# ESP01M_Carrier.net
KiCad netlist of a schematic drawn in EAGLE
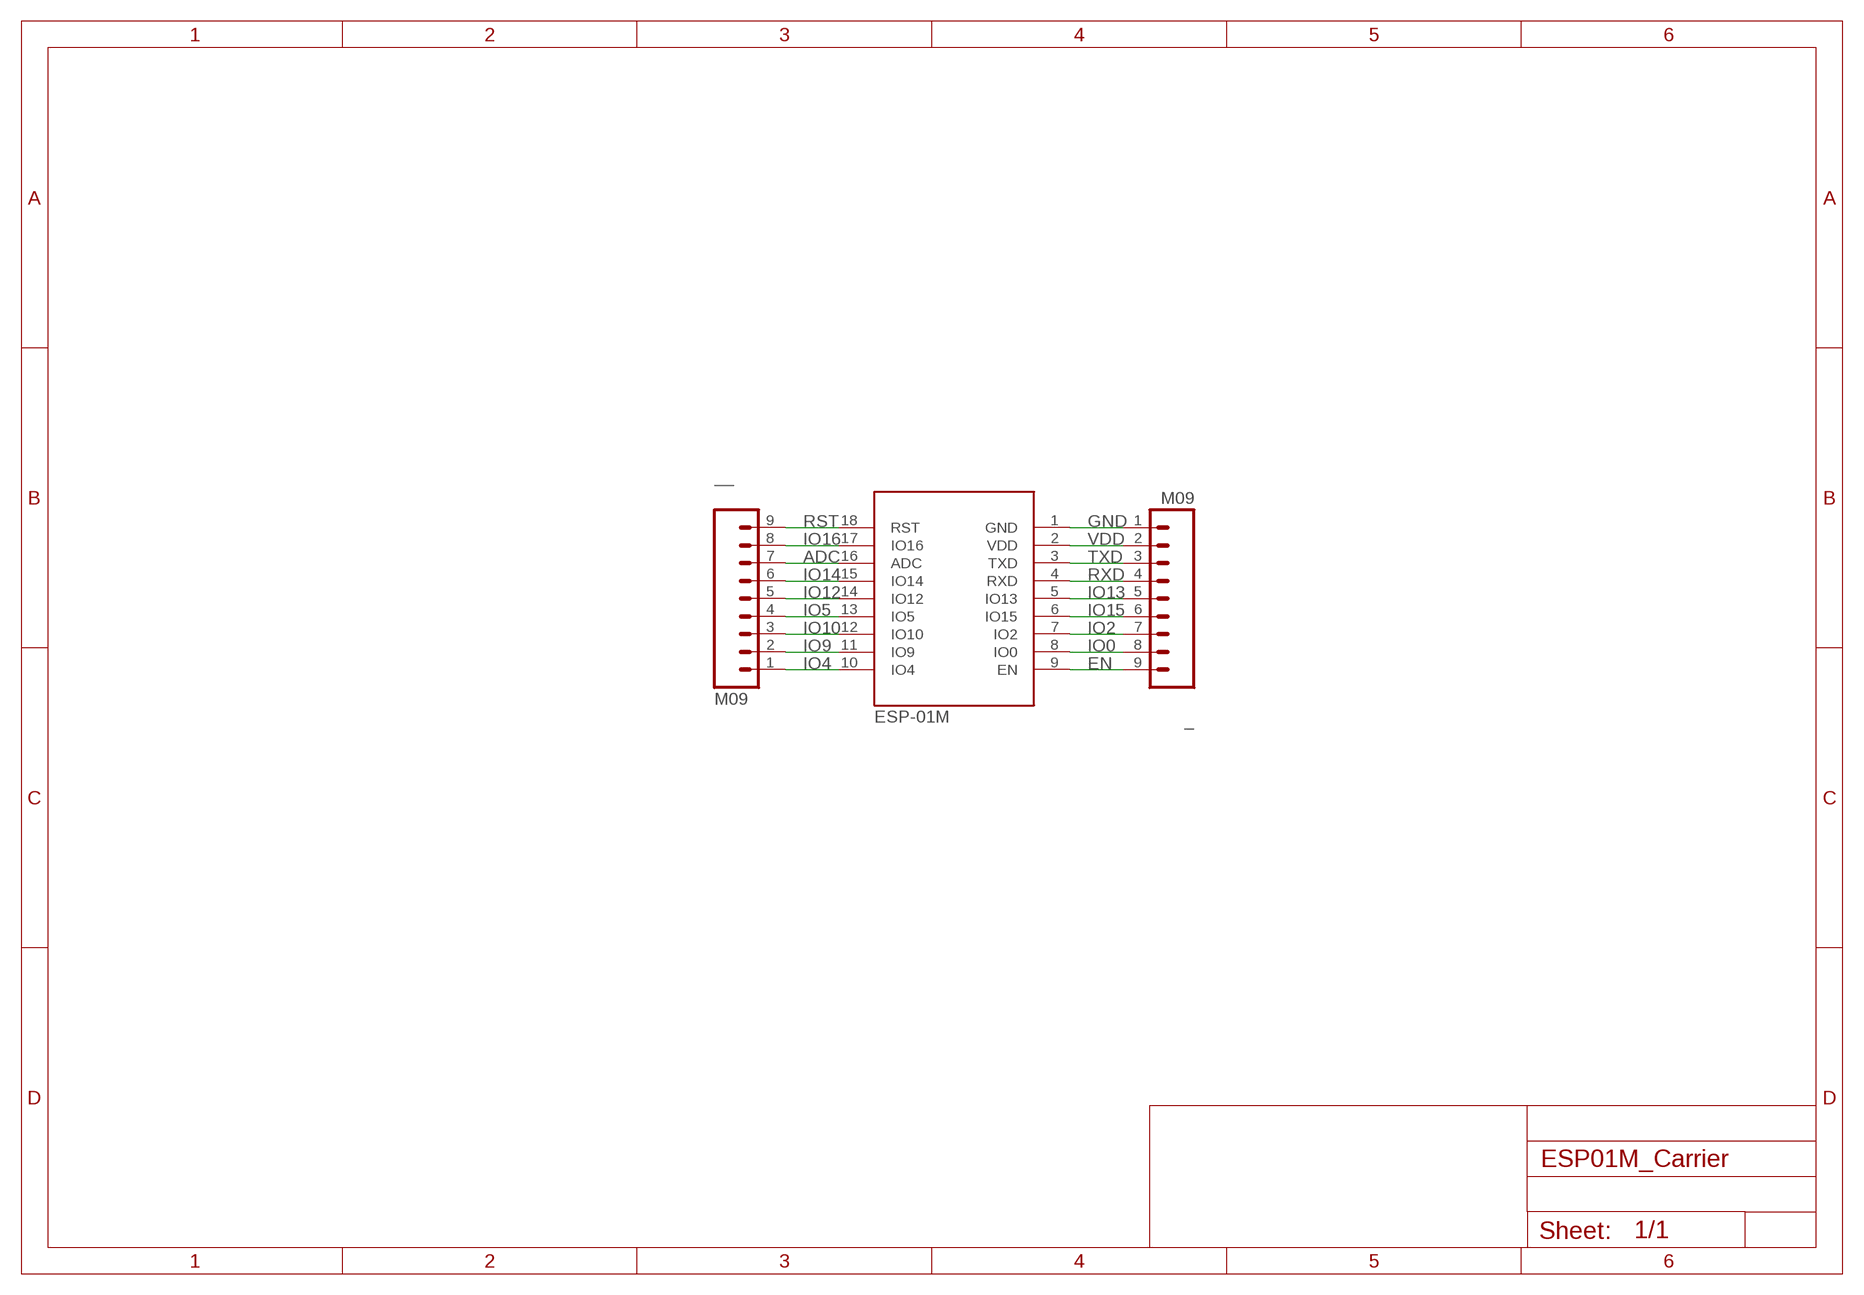
[diagram p0: schematic, sheet 1]

(export (version "E")
  (design (tool "Eeschema 10.0.6"))
  (components
    (comp (ref "ESP-01M")
      (value "ESP-01M")
      (footprint "eagle-import:ESP-01M")
      (libsource (lib "eagle-import") (part "ESP-01M"))
    )
    (comp (ref "_")
      (value "M09")
      (footprint "eagle-import:1X09")
      (libsource (lib "eagle-import") (part "M09"))
    )
    (comp (ref "__")
      (value "M09")
      (footprint "eagle-import:1X09")
      (libsource (lib "eagle-import") (part "M09"))
    )
  )
  (nets
    (net (code "1") (name "/ADC") (class "Default")
      (node (ref "ESP-01M") (pin "16") (pinfunction "ADC_16") (pintype "bidirectional"))
      (node (ref "__") (pin "7") (pinfunction "7_7") (pintype "passive"))
    )
    (net (code "2") (name "/EN") (class "Default")
      (node (ref "ESP-01M") (pin "9") (pinfunction "EN_9") (pintype "input"))
      (node (ref "_") (pin "9") (pinfunction "9_9") (pintype "passive"))
    )
    (net (code "3") (name "/GND") (class "Default")
      (node (ref "ESP-01M") (pin "1") (pinfunction "GND_1") (pintype "power_in"))
      (node (ref "_") (pin "1") (pinfunction "1_1") (pintype "passive"))
    )
    (net (code "4") (name "/IO0") (class "Default")
      (node (ref "ESP-01M") (pin "8") (pinfunction "IO0_8") (pintype "bidirectional"))
      (node (ref "_") (pin "8") (pinfunction "8_8") (pintype "passive"))
    )
    (net (code "5") (name "/IO2") (class "Default")
      (node (ref "ESP-01M") (pin "7") (pinfunction "IO2_7") (pintype "bidirectional"))
      (node (ref "_") (pin "7") (pinfunction "7_7") (pintype "passive"))
    )
    (net (code "6") (name "/IO4") (class "Default")
      (node (ref "ESP-01M") (pin "10") (pinfunction "IO4_10") (pintype "bidirectional"))
      (node (ref "__") (pin "1") (pinfunction "1_1") (pintype "passive"))
    )
    (net (code "7") (name "/IO5") (class "Default")
      (node (ref "ESP-01M") (pin "13") (pinfunction "IO5_13") (pintype "bidirectional"))
      (node (ref "__") (pin "4") (pinfunction "4_4") (pintype "passive"))
    )
    (net (code "8") (name "/IO9") (class "Default")
      (node (ref "ESP-01M") (pin "11") (pinfunction "IO9_11") (pintype "bidirectional"))
      (node (ref "__") (pin "2") (pinfunction "2_2") (pintype "passive"))
    )
    (net (code "9") (name "/IO10") (class "Default")
      (node (ref "ESP-01M") (pin "12") (pinfunction "IO10_12") (pintype "bidirectional"))
      (node (ref "__") (pin "3") (pinfunction "3_3") (pintype "passive"))
    )
    (net (code "10") (name "/IO12") (class "Default")
      (node (ref "ESP-01M") (pin "14") (pinfunction "IO12_14") (pintype "bidirectional"))
      (node (ref "__") (pin "5") (pinfunction "5_5") (pintype "passive"))
    )
    (net (code "11") (name "/IO13") (class "Default")
      (node (ref "ESP-01M") (pin "5") (pinfunction "IO13_5") (pintype "bidirectional"))
      (node (ref "_") (pin "5") (pinfunction "5_5") (pintype "passive"))
    )
    (net (code "12") (name "/IO14") (class "Default")
      (node (ref "ESP-01M") (pin "15") (pinfunction "IO14_15") (pintype "bidirectional"))
      (node (ref "__") (pin "6") (pinfunction "6_6") (pintype "passive"))
    )
    (net (code "13") (name "/IO15") (class "Default")
      (node (ref "ESP-01M") (pin "6") (pinfunction "IO15_6") (pintype "bidirectional"))
      (node (ref "_") (pin "6") (pinfunction "6_6") (pintype "passive"))
    )
    (net (code "14") (name "/IO16") (class "Default")
      (node (ref "ESP-01M") (pin "17") (pinfunction "IO16_17") (pintype "bidirectional"))
      (node (ref "__") (pin "8") (pinfunction "8_8") (pintype "passive"))
    )
    (net (code "15") (name "/RST") (class "Default")
      (node (ref "ESP-01M") (pin "18") (pinfunction "RST_18") (pintype "input"))
      (node (ref "__") (pin "9") (pinfunction "9_9") (pintype "passive"))
    )
    (net (code "16") (name "/RXD") (class "Default")
      (node (ref "ESP-01M") (pin "4") (pinfunction "RXD_4") (pintype "input"))
      (node (ref "_") (pin "4") (pinfunction "4_4") (pintype "passive"))
    )
    (net (code "17") (name "/TXD") (class "Default")
      (node (ref "ESP-01M") (pin "3") (pinfunction "TXD_3") (pintype "output"))
      (node (ref "_") (pin "3") (pinfunction "3_3") (pintype "passive"))
    )
    (net (code "18") (name "/VDD") (class "Default")
      (node (ref "ESP-01M") (pin "2") (pinfunction "VDD_2") (pintype "passive"))
      (node (ref "_") (pin "2") (pinfunction "2_2") (pintype "passive"))
    )
  )
)
